# Servo_Cape.net
KiCad netlist of a schematic drawn in EAGLE
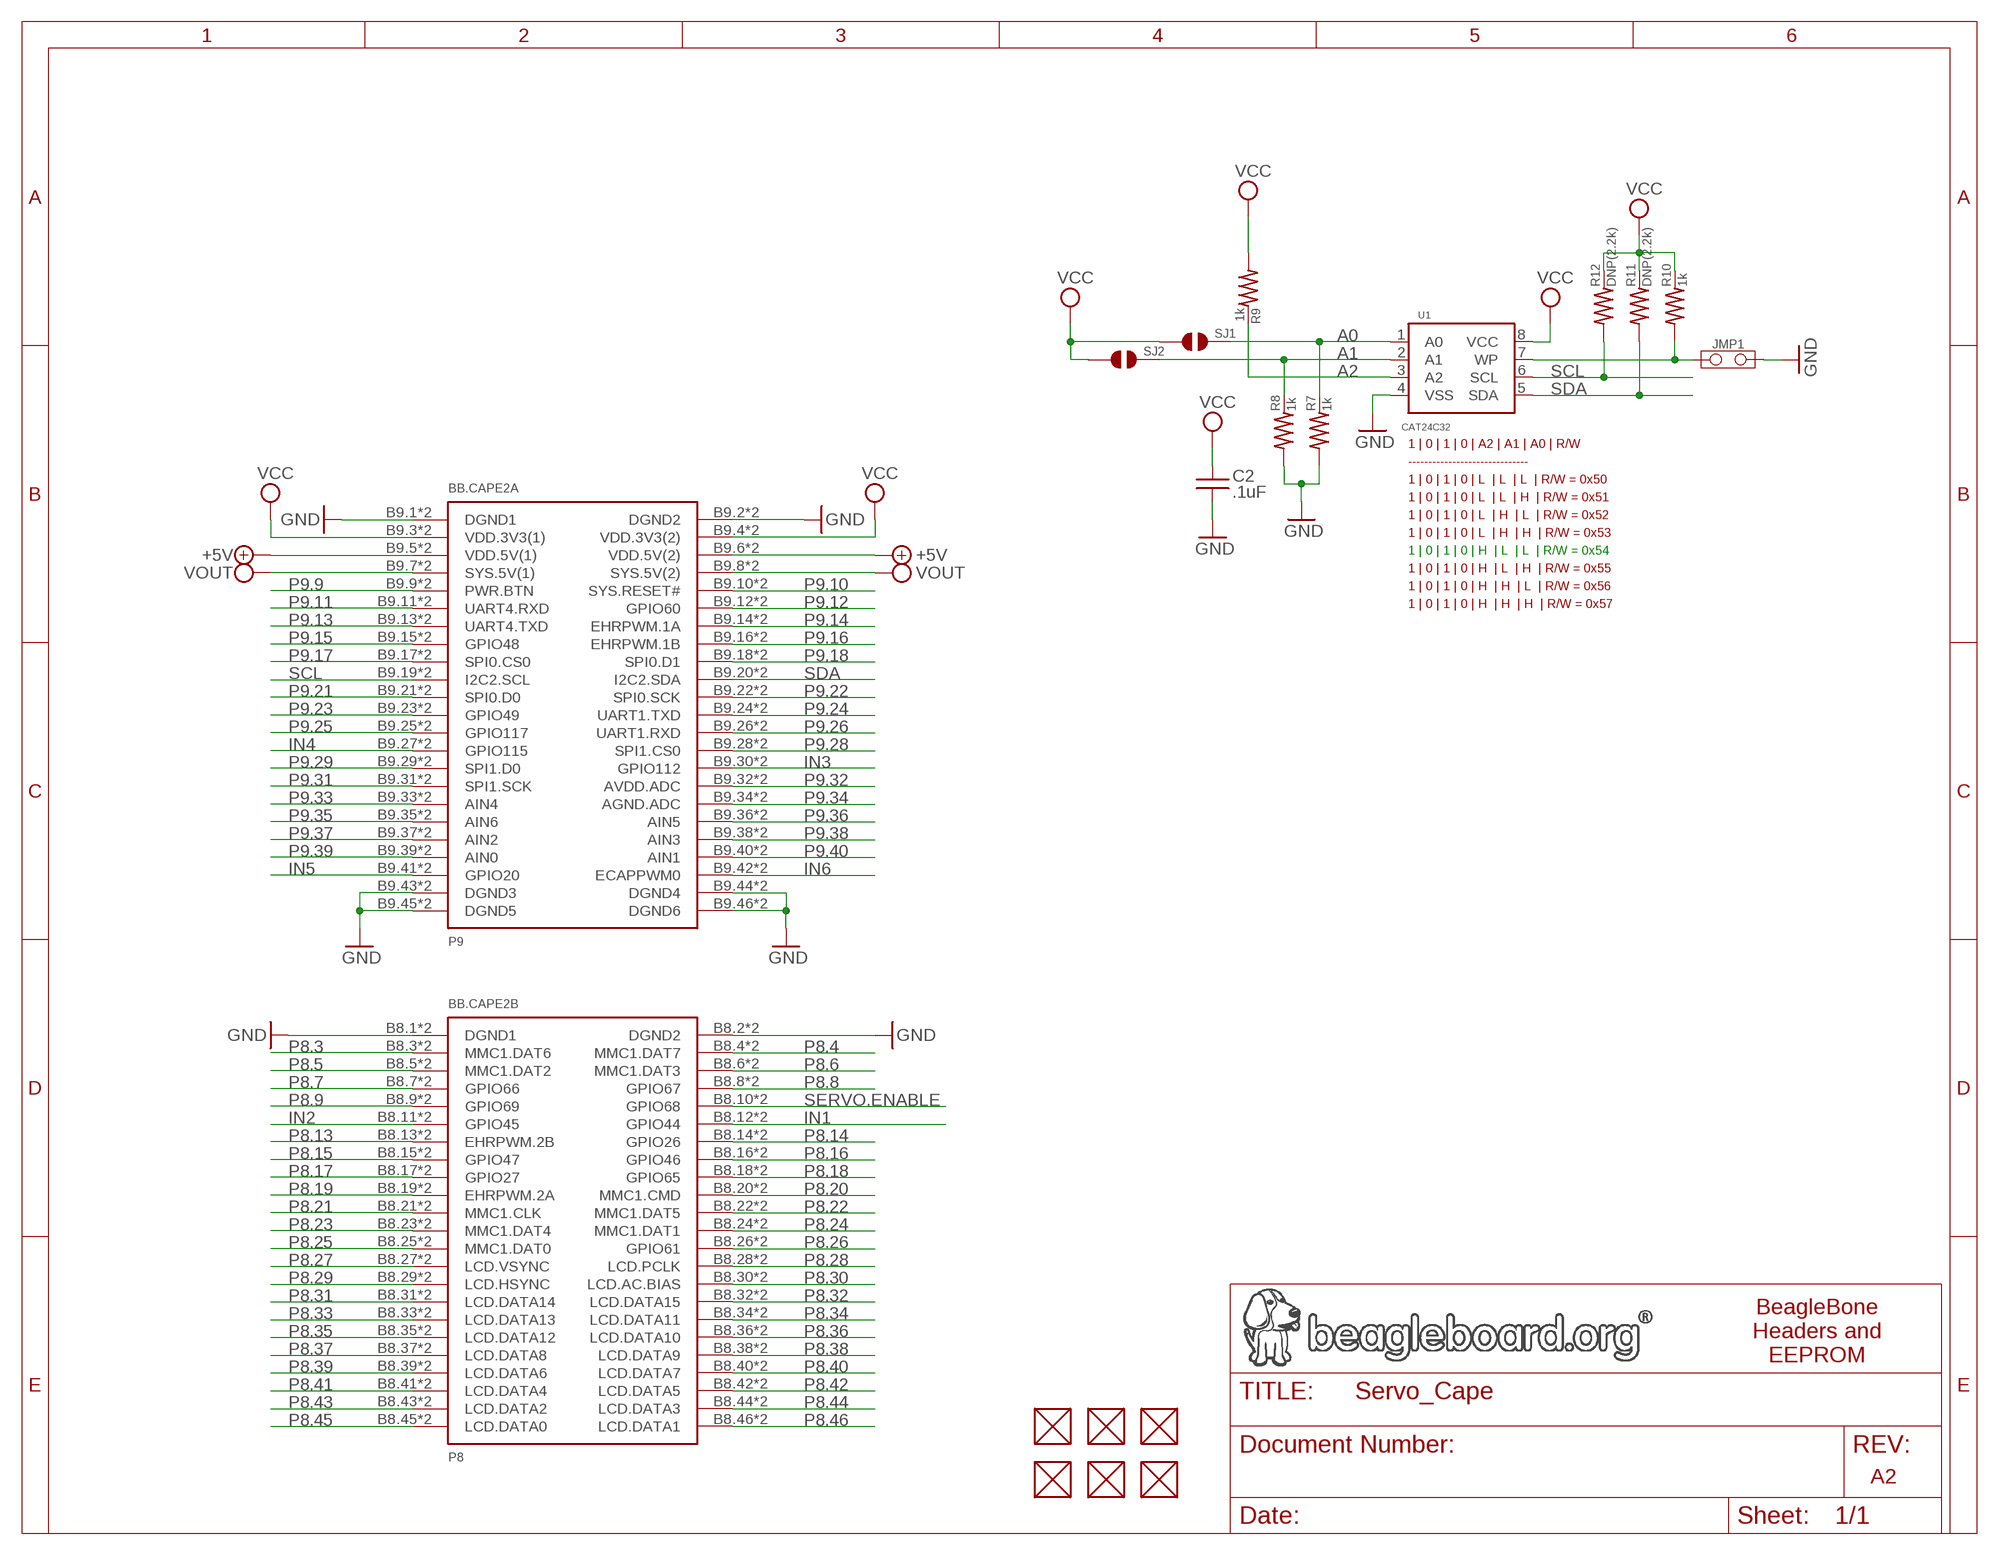
[diagram p0: schematic, sheet 1, part 1 of 2]
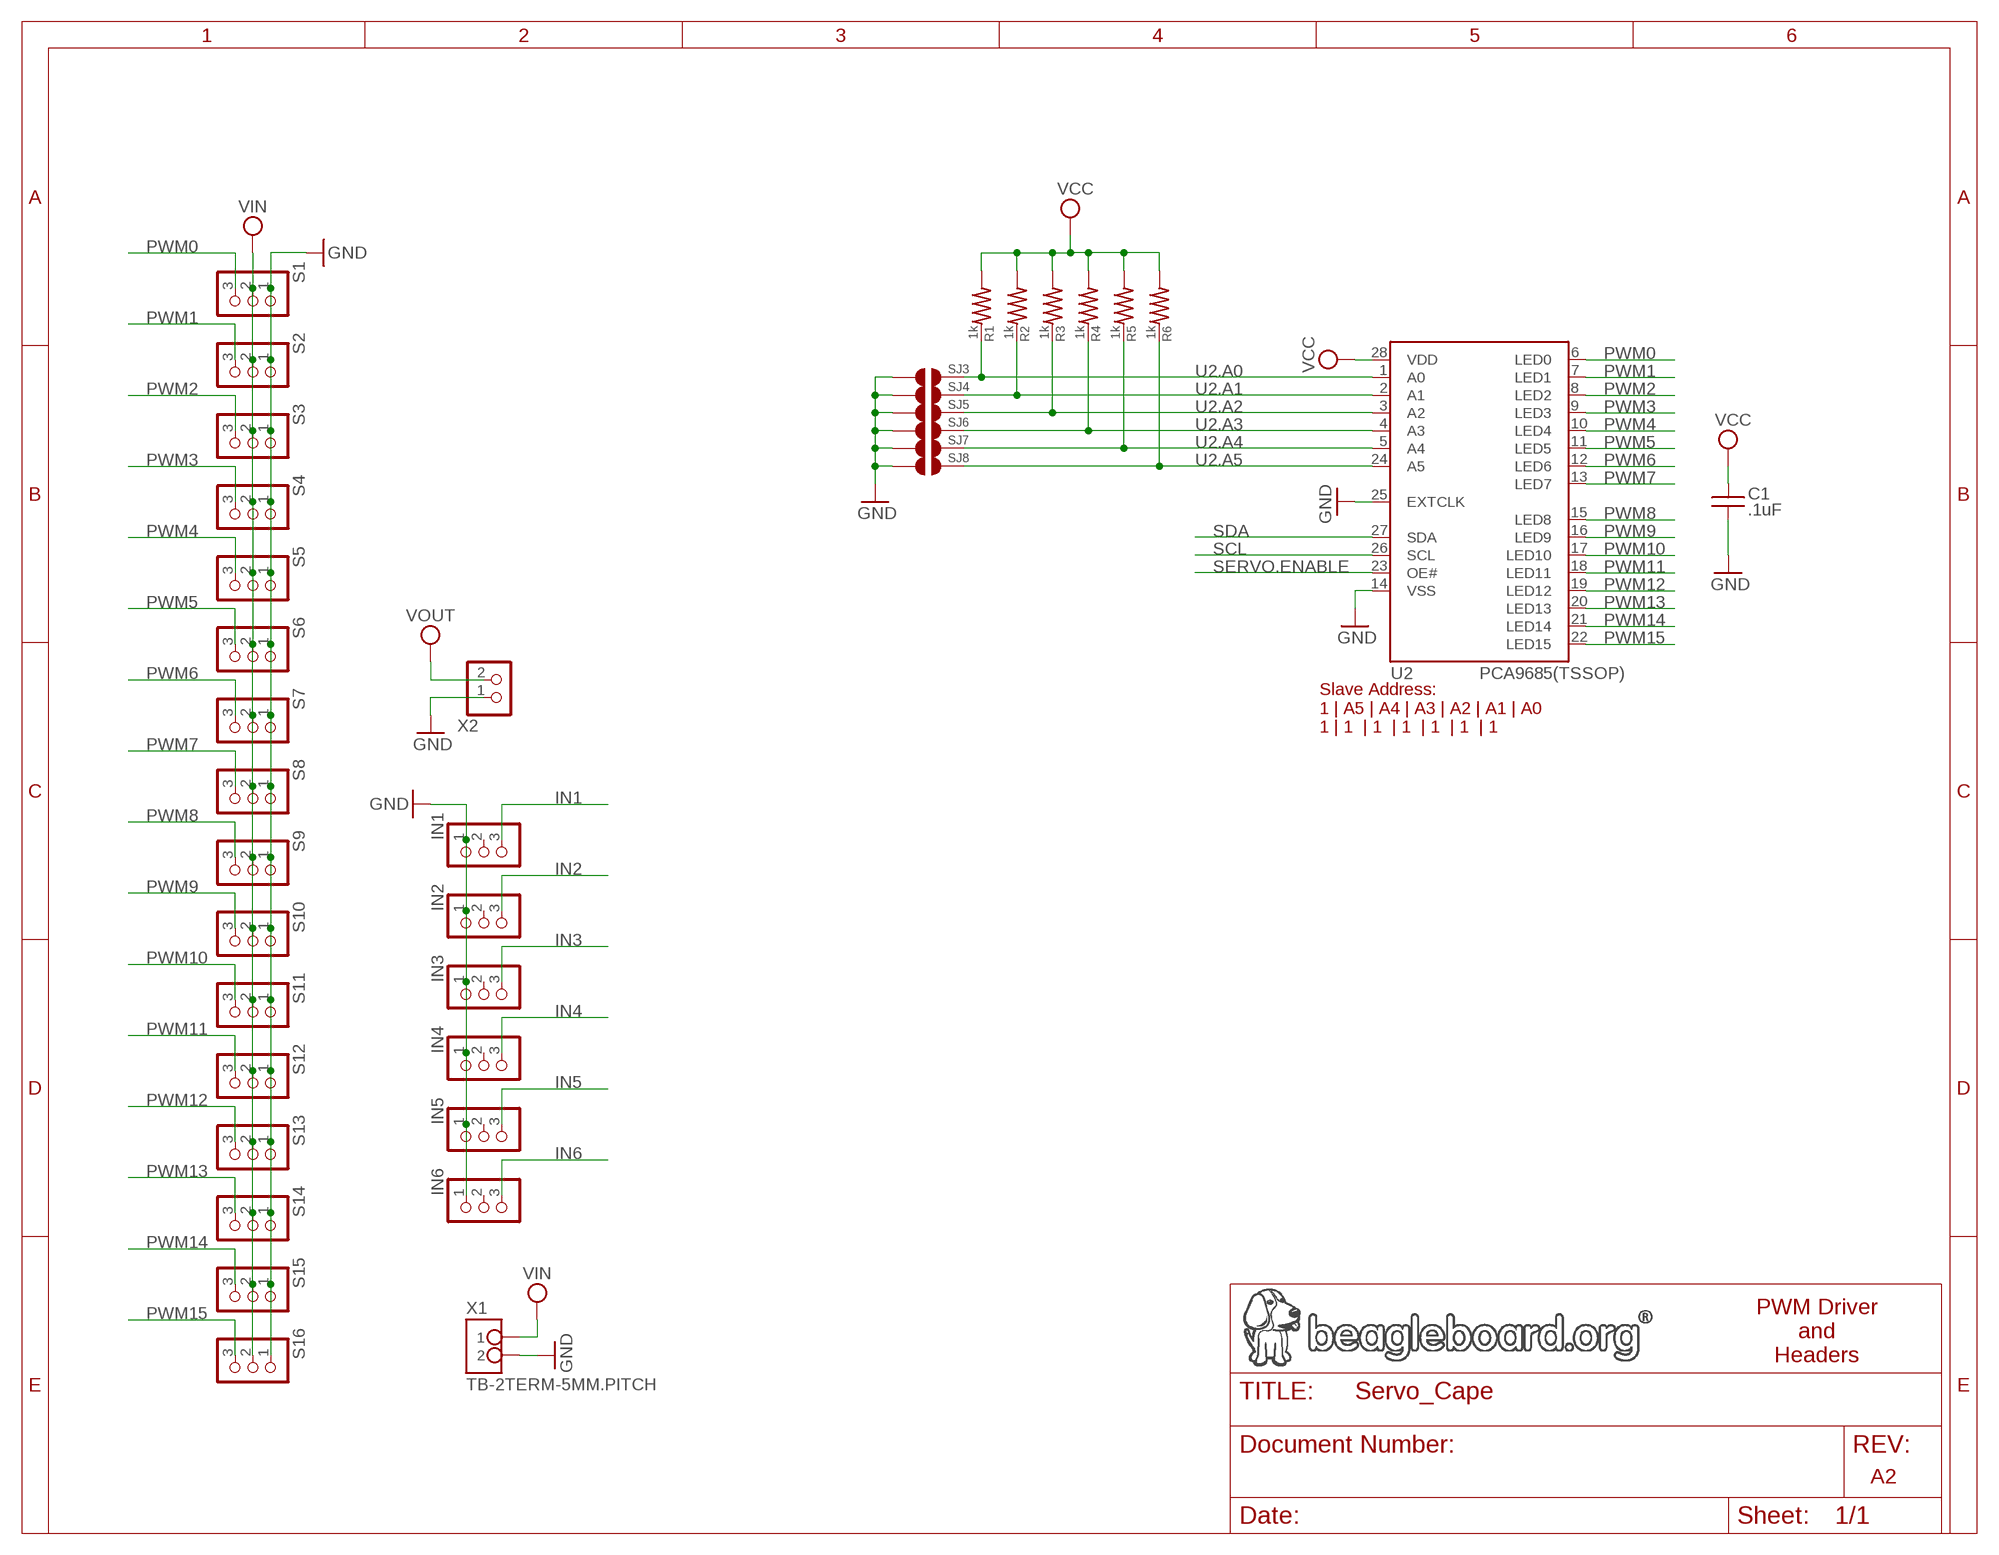
[diagram p1: schematic, sheet 1, part 2 of 2]

(export (version "E")
  (design (tool "Eeschema 10.0.6"))
  (components
    (comp (ref "BB.CAPE2")
      (value "BEAGLEBONE.CAPE.TOP/BOTTOM-PADS")
      (footprint "eagle-import:BEAGLEBONE.CAPE.TOP_BOTTOM-PADS")
      (libsource (lib "eagle-import") (part "BEAGLEBONE.CAPE.TOP/BOTTOM-PADS"))
    )
    (comp (ref "C1")
      (value ".1uF")
      (footprint "eagle-import:0402")
      (libsource (lib "eagle-import") (part "CAPACITOR-(INCH)-0402"))
    )
    (comp (ref "C2")
      (value ".1uF")
      (footprint "eagle-import:0402")
      (libsource (lib "eagle-import") (part "CAPACITOR-(INCH)-0402"))
    )
    (comp (ref "FUD1")
      (value "FIDUCIAL")
      (footprint "eagle-import:FIDUCIAL_40MIL")
      (libsource (lib "eagle-import") (part "FIDUCIAL"))
    )
    (comp (ref "FUD2")
      (value "FIDUCIAL")
      (footprint "eagle-import:FIDUCIAL_40MIL")
      (libsource (lib "eagle-import") (part "FIDUCIAL"))
    )
    (comp (ref "FUD3")
      (value "FIDUCIAL")
      (footprint "eagle-import:FIDUCIAL_40MIL")
      (libsource (lib "eagle-import") (part "FIDUCIAL"))
    )
    (comp (ref "FUD4")
      (value "FIDUCIAL")
      (footprint "eagle-import:FIDUCIAL_40MIL")
      (libsource (lib "eagle-import") (part "FIDUCIAL"))
    )
    (comp (ref "FUD5")
      (value "FIDUCIAL")
      (footprint "eagle-import:FIDUCIAL_40MIL")
      (libsource (lib "eagle-import") (part "FIDUCIAL"))
    )
    (comp (ref "FUD6")
      (value "FIDUCIAL")
      (footprint "eagle-import:FIDUCIAL_40MIL")
      (libsource (lib "eagle-import") (part "FIDUCIAL"))
    )
    (comp (ref "IN1")
      (value "1X3-(INCH)-0.1-TH-(35-MIL.DIA)")
      (footprint "eagle-import:TH-1X3-(35-MIL.DIA)")
      (libsource (lib "eagle-import") (part "1X3-(INCH)-0.1-TH-(35-MIL.DIA)"))
    )
    (comp (ref "IN2")
      (value "1X3-(INCH)-0.1-TH-(35-MIL.DIA)")
      (footprint "eagle-import:TH-1X3-(35-MIL.DIA)")
      (libsource (lib "eagle-import") (part "1X3-(INCH)-0.1-TH-(35-MIL.DIA)"))
    )
    (comp (ref "IN3")
      (value "1X3-(INCH)-0.1-TH-(35-MIL.DIA)")
      (footprint "eagle-import:TH-1X3-(35-MIL.DIA)")
      (libsource (lib "eagle-import") (part "1X3-(INCH)-0.1-TH-(35-MIL.DIA)"))
    )
    (comp (ref "IN4")
      (value "1X3-(INCH)-0.1-TH-(35-MIL.DIA)")
      (footprint "eagle-import:TH-1X3-(35-MIL.DIA)")
      (libsource (lib "eagle-import") (part "1X3-(INCH)-0.1-TH-(35-MIL.DIA)"))
    )
    (comp (ref "IN5")
      (value "1X3-(INCH)-0.1-TH-(35-MIL.DIA)")
      (footprint "eagle-import:TH-1X3-(35-MIL.DIA)")
      (libsource (lib "eagle-import") (part "1X3-(INCH)-0.1-TH-(35-MIL.DIA)"))
    )
    (comp (ref "IN6")
      (value "1X3-(INCH)-0.1-TH-(35-MIL.DIA)")
      (footprint "eagle-import:TH-1X3-(35-MIL.DIA)")
      (libsource (lib "eagle-import") (part "1X3-(INCH)-0.1-TH-(35-MIL.DIA)"))
    )
    (comp (ref "JMP1")
      (value "JUMPER-(X2)")
      (footprint "eagle-import:JUMPER-(X2)")
      (libsource (lib "eagle-import") (part "JUMPER-(X2)"))
    )
    (comp (ref "R1")
      (value "1k")
      (footprint "eagle-import:0402")
      (libsource (lib "eagle-import") (part "RESISTOR-(INCH)-0402"))
    )
    (comp (ref "R2")
      (value "1k")
      (footprint "eagle-import:0402")
      (libsource (lib "eagle-import") (part "RESISTOR-(INCH)-0402"))
    )
    (comp (ref "R3")
      (value "1k")
      (footprint "eagle-import:0402")
      (libsource (lib "eagle-import") (part "RESISTOR-(INCH)-0402"))
    )
    (comp (ref "R4")
      (value "1k")
      (footprint "eagle-import:0402")
      (libsource (lib "eagle-import") (part "RESISTOR-(INCH)-0402"))
    )
    (comp (ref "R5")
      (value "1k")
      (footprint "eagle-import:0402")
      (libsource (lib "eagle-import") (part "RESISTOR-(INCH)-0402"))
    )
    (comp (ref "R6")
      (value "1k")
      (footprint "eagle-import:0402")
      (libsource (lib "eagle-import") (part "RESISTOR-(INCH)-0402"))
    )
    (comp (ref "R7")
      (value "1k")
      (footprint "eagle-import:0402")
      (libsource (lib "eagle-import") (part "RESISTOR-(INCH)-0402"))
    )
    (comp (ref "R8")
      (value "1k")
      (footprint "eagle-import:0402")
      (libsource (lib "eagle-import") (part "RESISTOR-(INCH)-0402"))
    )
    (comp (ref "R9")
      (value "1k")
      (footprint "eagle-import:0402")
      (libsource (lib "eagle-import") (part "RESISTOR-(INCH)-0402"))
    )
    (comp (ref "R10")
      (value "1k")
      (footprint "eagle-import:0402")
      (libsource (lib "eagle-import") (part "RESISTOR-(INCH)-0402"))
    )
    (comp (ref "R11")
      (value "DNP(2.2k)")
      (footprint "eagle-import:0402")
      (libsource (lib "eagle-import") (part "RESISTOR-(INCH)-0402"))
    )
    (comp (ref "R12")
      (value "DNP(2.2k)")
      (footprint "eagle-import:0402")
      (libsource (lib "eagle-import") (part "RESISTOR-(INCH)-0402"))
    )
    (comp (ref "S1")
      (value "1X3-(INCH)-0.1-TH-(35-MIL.DIA)")
      (footprint "eagle-import:TH-1X3-(35-MIL.DIA)")
      (libsource (lib "eagle-import") (part "1X3-(INCH)-0.1-TH-(35-MIL.DIA)"))
    )
    (comp (ref "S2")
      (value "1X3-(INCH)-0.1-TH-(35-MIL.DIA)")
      (footprint "eagle-import:TH-1X3-(35-MIL.DIA)")
      (libsource (lib "eagle-import") (part "1X3-(INCH)-0.1-TH-(35-MIL.DIA)"))
    )
    (comp (ref "S3")
      (value "1X3-(INCH)-0.1-TH-(35-MIL.DIA)")
      (footprint "eagle-import:TH-1X3-(35-MIL.DIA)")
      (libsource (lib "eagle-import") (part "1X3-(INCH)-0.1-TH-(35-MIL.DIA)"))
    )
    (comp (ref "S4")
      (value "1X3-(INCH)-0.1-TH-(35-MIL.DIA)")
      (footprint "eagle-import:TH-1X3-(35-MIL.DIA)")
      (libsource (lib "eagle-import") (part "1X3-(INCH)-0.1-TH-(35-MIL.DIA)"))
    )
    (comp (ref "S5")
      (value "1X3-(INCH)-0.1-TH-(35-MIL.DIA)")
      (footprint "eagle-import:TH-1X3-(35-MIL.DIA)")
      (libsource (lib "eagle-import") (part "1X3-(INCH)-0.1-TH-(35-MIL.DIA)"))
    )
    (comp (ref "S6")
      (value "1X3-(INCH)-0.1-TH-(35-MIL.DIA)")
      (footprint "eagle-import:TH-1X3-(35-MIL.DIA)")
      (libsource (lib "eagle-import") (part "1X3-(INCH)-0.1-TH-(35-MIL.DIA)"))
    )
    (comp (ref "S7")
      (value "1X3-(INCH)-0.1-TH-(35-MIL.DIA)")
      (footprint "eagle-import:TH-1X3-(35-MIL.DIA)")
      (libsource (lib "eagle-import") (part "1X3-(INCH)-0.1-TH-(35-MIL.DIA)"))
    )
    (comp (ref "S8")
      (value "1X3-(INCH)-0.1-TH-(35-MIL.DIA)")
      (footprint "eagle-import:TH-1X3-(35-MIL.DIA)")
      (libsource (lib "eagle-import") (part "1X3-(INCH)-0.1-TH-(35-MIL.DIA)"))
    )
    (comp (ref "S9")
      (value "1X3-(INCH)-0.1-TH-(35-MIL.DIA)")
      (footprint "eagle-import:TH-1X3-(35-MIL.DIA)")
      (libsource (lib "eagle-import") (part "1X3-(INCH)-0.1-TH-(35-MIL.DIA)"))
    )
    (comp (ref "S10")
      (value "1X3-(INCH)-0.1-TH-(35-MIL.DIA)")
      (footprint "eagle-import:TH-1X3-(35-MIL.DIA)")
      (libsource (lib "eagle-import") (part "1X3-(INCH)-0.1-TH-(35-MIL.DIA)"))
    )
    (comp (ref "S11")
      (value "1X3-(INCH)-0.1-TH-(35-MIL.DIA)")
      (footprint "eagle-import:TH-1X3-(35-MIL.DIA)")
      (libsource (lib "eagle-import") (part "1X3-(INCH)-0.1-TH-(35-MIL.DIA)"))
    )
    (comp (ref "S12")
      (value "1X3-(INCH)-0.1-TH-(35-MIL.DIA)")
      (footprint "eagle-import:TH-1X3-(35-MIL.DIA)")
      (libsource (lib "eagle-import") (part "1X3-(INCH)-0.1-TH-(35-MIL.DIA)"))
    )
    (comp (ref "S13")
      (value "1X3-(INCH)-0.1-TH-(35-MIL.DIA)")
      (footprint "eagle-import:TH-1X3-(35-MIL.DIA)")
      (libsource (lib "eagle-import") (part "1X3-(INCH)-0.1-TH-(35-MIL.DIA)"))
    )
    (comp (ref "S14")
      (value "1X3-(INCH)-0.1-TH-(35-MIL.DIA)")
      (footprint "eagle-import:TH-1X3-(35-MIL.DIA)")
      (libsource (lib "eagle-import") (part "1X3-(INCH)-0.1-TH-(35-MIL.DIA)"))
    )
    (comp (ref "S15")
      (value "1X3-(INCH)-0.1-TH-(35-MIL.DIA)")
      (footprint "eagle-import:TH-1X3-(35-MIL.DIA)")
      (libsource (lib "eagle-import") (part "1X3-(INCH)-0.1-TH-(35-MIL.DIA)"))
    )
    (comp (ref "S16")
      (value "1X3-(INCH)-0.1-TH-(35-MIL.DIA)")
      (footprint "eagle-import:TH-1X3-(35-MIL.DIA)")
      (libsource (lib "eagle-import") (part "1X3-(INCH)-0.1-TH-(35-MIL.DIA)"))
    )
    (comp (ref "SJ1")
      (value "SOLDER.JOINT-(INCH)-0402")
      (footprint "eagle-import:SOLDER.JOINT(0402)")
      (libsource (lib "eagle-import") (part "SOLDER.JOINT-(INCH)-0402"))
    )
    (comp (ref "SJ2")
      (value "SOLDER.JOINT-(INCH)-0402")
      (footprint "eagle-import:SOLDER.JOINT(0402)")
      (libsource (lib "eagle-import") (part "SOLDER.JOINT-(INCH)-0402"))
    )
    (comp (ref "SJ3")
      (value "SOLDER.JOINT-(INCH)-0402")
      (footprint "eagle-import:SOLDER.JOINT(0402)")
      (libsource (lib "eagle-import") (part "SOLDER.JOINT-(INCH)-0402"))
    )
    (comp (ref "SJ4")
      (value "SOLDER.JOINT-(INCH)-0402")
      (footprint "eagle-import:SOLDER.JOINT(0402)")
      (libsource (lib "eagle-import") (part "SOLDER.JOINT-(INCH)-0402"))
    )
    (comp (ref "SJ5")
      (value "SOLDER.JOINT-(INCH)-0402")
      (footprint "eagle-import:SOLDER.JOINT(0402)")
      (libsource (lib "eagle-import") (part "SOLDER.JOINT-(INCH)-0402"))
    )
    (comp (ref "SJ6")
      (value "SOLDER.JOINT-(INCH)-0402")
      (footprint "eagle-import:SOLDER.JOINT(0402)")
      (libsource (lib "eagle-import") (part "SOLDER.JOINT-(INCH)-0402"))
    )
    (comp (ref "SJ7")
      (value "SOLDER.JOINT-(INCH)-0402")
      (footprint "eagle-import:SOLDER.JOINT(0402)")
      (libsource (lib "eagle-import") (part "SOLDER.JOINT-(INCH)-0402"))
    )
    (comp (ref "SJ8")
      (value "SOLDER.JOINT-(INCH)-0402")
      (footprint "eagle-import:SOLDER.JOINT(0402)")
      (libsource (lib "eagle-import") (part "SOLDER.JOINT-(INCH)-0402"))
    )
    (comp (ref "U1")
      (value "CAT24C32")
      (footprint "eagle-import:UDFN8,2X3(ON-SEMI)")
      (libsource (lib "eagle-import") (part "CAT24C32"))
    )
    (comp (ref "U2")
      (value "PCA9685(TSSOP)")
      (footprint "eagle-import:TSSOP28(NXP)")
      (libsource (lib "eagle-import") (part "PCA9685(TSSOP)"))
    )
    (comp (ref "X1")
      (value "TB-2TERM-5MM.PITCH")
      (footprint "eagle-import:TERMINAL.BLOCK-2TERM-5MM.PITCH")
      (libsource (lib "eagle-import") (part "TB-2TERM-5MM.PITCH"))
    )
    (comp (ref "X2")
      (value "1X2-(INCH)-0.1-TH-(35-MIL.DIA)")
      (footprint "eagle-import:TH-1X2-(35-MIL.DIA)")
      (libsource (lib "eagle-import") (part "1X2-(INCH)-0.1-TH-(35-MIL.DIA)"))
    )
  )
  (nets
    (net (code "1") (name "+5V") (class "Default")
      (node (ref "BB.CAPE2") (pin "B9.5") (pinfunction "VDD.5V(1)_B9.5") (pintype "bidirectional"))
      (node (ref "BB.CAPE2") (pin "B9.6") (pinfunction "VDD.5V(2)_B9.6") (pintype "bidirectional"))
      (node (ref "BB.CAPE2") (pin "T9.5") (pinfunction "VDD.5V(1)_T9.5") (pintype "bidirectional"))
      (node (ref "BB.CAPE2") (pin "T9.6") (pinfunction "VDD.5V(2)_T9.6") (pintype "bidirectional"))
    )
    (net (code "2") (name "/A0") (class "Default")
      (node (ref "R7") (pin "2") (pinfunction "2_2") (pintype "bidirectional"))
      (node (ref "SJ1") (pin "2") (pinfunction "2_2") (pintype "bidirectional"))
      (node (ref "U1") (pin "1") (pinfunction "A0_1") (pintype "bidirectional"))
    )
    (net (code "3") (name "/A1") (class "Default")
      (node (ref "R8") (pin "2") (pinfunction "2_2") (pintype "bidirectional"))
      (node (ref "SJ2") (pin "2") (pinfunction "2_2") (pintype "bidirectional"))
      (node (ref "U1") (pin "2") (pinfunction "A1_2") (pintype "bidirectional"))
    )
    (net (code "4") (name "/A2") (class "Default")
      (node (ref "R9") (pin "2") (pinfunction "2_2") (pintype "bidirectional"))
      (node (ref "U1") (pin "3") (pinfunction "A2_3") (pintype "bidirectional"))
    )
    (net (code "5") (name "/IN1") (class "Default")
      (node (ref "BB.CAPE2") (pin "B8.12") (pinfunction "GPIO44_B8.12") (pintype "bidirectional"))
      (node (ref "BB.CAPE2") (pin "T8.12") (pinfunction "GPIO44_T8.12") (pintype "bidirectional"))
      (node (ref "IN1") (pin "3") (pinfunction "3_3") (pintype "passive"))
    )
    (net (code "6") (name "/IN2") (class "Default")
      (node (ref "BB.CAPE2") (pin "B8.11") (pinfunction "GPIO45_B8.11") (pintype "bidirectional"))
      (node (ref "BB.CAPE2") (pin "T8.11") (pinfunction "GPIO45_T8.11") (pintype "bidirectional"))
      (node (ref "IN2") (pin "3") (pinfunction "3_3") (pintype "passive"))
    )
    (net (code "7") (name "/IN3") (class "Default")
      (node (ref "BB.CAPE2") (pin "B9.30") (pinfunction "GPIO112_B9.30") (pintype "bidirectional"))
      (node (ref "BB.CAPE2") (pin "T9.30") (pinfunction "GPIO112_T9.30") (pintype "bidirectional"))
      (node (ref "IN3") (pin "3") (pinfunction "3_3") (pintype "passive"))
    )
    (net (code "8") (name "/IN4") (class "Default")
      (node (ref "BB.CAPE2") (pin "B9.27") (pinfunction "GPIO115_B9.27") (pintype "bidirectional"))
      (node (ref "BB.CAPE2") (pin "T9.27") (pinfunction "GPIO115_T9.27") (pintype "bidirectional"))
      (node (ref "IN4") (pin "3") (pinfunction "3_3") (pintype "passive"))
    )
    (net (code "9") (name "/IN5") (class "Default")
      (node (ref "BB.CAPE2") (pin "B9.41") (pinfunction "GPIO20_B9.41") (pintype "bidirectional"))
      (node (ref "BB.CAPE2") (pin "T9.41") (pinfunction "GPIO20_T9.41") (pintype "bidirectional"))
      (node (ref "IN5") (pin "3") (pinfunction "3_3") (pintype "passive"))
    )
    (net (code "10") (name "/IN6") (class "Default")
      (node (ref "BB.CAPE2") (pin "B9.42") (pinfunction "ECAPPWM0_B9.42") (pintype "bidirectional"))
      (node (ref "BB.CAPE2") (pin "T9.42") (pinfunction "ECAPPWM0_T9.42") (pintype "bidirectional"))
      (node (ref "IN6") (pin "3") (pinfunction "3_3") (pintype "passive"))
    )
    (net (code "11") (name "/P8.3") (class "Default")
      (node (ref "BB.CAPE2") (pin "B8.3") (pinfunction "MMC1.DAT6_B8.3") (pintype "bidirectional"))
      (node (ref "BB.CAPE2") (pin "T8.3") (pinfunction "MMC1.DAT6_T8.3") (pintype "bidirectional"))
    )
    (net (code "12") (name "/P8.4") (class "Default")
      (node (ref "BB.CAPE2") (pin "B8.4") (pinfunction "MMC1.DAT7_B8.4") (pintype "bidirectional"))
      (node (ref "BB.CAPE2") (pin "T8.4") (pinfunction "MMC1.DAT7_T8.4") (pintype "bidirectional"))
    )
    (net (code "13") (name "/P8.5") (class "Default")
      (node (ref "BB.CAPE2") (pin "B8.5") (pinfunction "MMC1.DAT2_B8.5") (pintype "bidirectional"))
      (node (ref "BB.CAPE2") (pin "T8.5") (pinfunction "MMC1.DAT2_T8.5") (pintype "bidirectional"))
    )
    (net (code "14") (name "/P8.6") (class "Default")
      (node (ref "BB.CAPE2") (pin "B8.6") (pinfunction "MMC1.DAT3_B8.6") (pintype "bidirectional"))
      (node (ref "BB.CAPE2") (pin "T8.6") (pinfunction "MMC1.DAT3_T8.6") (pintype "bidirectional"))
    )
    (net (code "15") (name "/P8.7") (class "Default")
      (node (ref "BB.CAPE2") (pin "B8.7") (pinfunction "GPIO66_B8.7") (pintype "bidirectional"))
      (node (ref "BB.CAPE2") (pin "T8.7") (pinfunction "GPIO66_T8.7") (pintype "bidirectional"))
    )
    (net (code "16") (name "/P8.8") (class "Default")
      (node (ref "BB.CAPE2") (pin "B8.8") (pinfunction "GPIO67_B8.8") (pintype "bidirectional"))
      (node (ref "BB.CAPE2") (pin "T8.8") (pinfunction "GPIO67_T8.8") (pintype "bidirectional"))
    )
    (net (code "17") (name "/P8.9") (class "Default")
      (node (ref "BB.CAPE2") (pin "B8.9") (pinfunction "GPIO69_B8.9") (pintype "bidirectional"))
      (node (ref "BB.CAPE2") (pin "T8.9") (pinfunction "GPIO69_T8.9") (pintype "bidirectional"))
    )
    (net (code "18") (name "/P8.13") (class "Default")
      (node (ref "BB.CAPE2") (pin "B8.13") (pinfunction "EHRPWM.2B_B8.13") (pintype "bidirectional"))
      (node (ref "BB.CAPE2") (pin "T8.13") (pinfunction "EHRPWM.2B_T8.13") (pintype "bidirectional"))
    )
    (net (code "19") (name "/P8.14") (class "Default")
      (node (ref "BB.CAPE2") (pin "B8.14") (pinfunction "GPIO26_B8.14") (pintype "bidirectional"))
      (node (ref "BB.CAPE2") (pin "T8.14") (pinfunction "GPIO26_T8.14") (pintype "bidirectional"))
    )
    (net (code "20") (name "/P8.15") (class "Default")
      (node (ref "BB.CAPE2") (pin "B8.15") (pinfunction "GPIO47_B8.15") (pintype "bidirectional"))
      (node (ref "BB.CAPE2") (pin "T8.15") (pinfunction "GPIO47_T8.15") (pintype "bidirectional"))
    )
    (net (code "21") (name "/P8.16") (class "Default")
      (node (ref "BB.CAPE2") (pin "B8.16") (pinfunction "GPIO46_B8.16") (pintype "bidirectional"))
      (node (ref "BB.CAPE2") (pin "T8.16") (pinfunction "GPIO46_T8.16") (pintype "bidirectional"))
    )
    (net (code "22") (name "/P8.17") (class "Default")
      (node (ref "BB.CAPE2") (pin "B8.17") (pinfunction "GPIO27_B8.17") (pintype "bidirectional"))
      (node (ref "BB.CAPE2") (pin "T8.17") (pinfunction "GPIO27_T8.17") (pintype "bidirectional"))
    )
    (net (code "23") (name "/P8.18") (class "Default")
      (node (ref "BB.CAPE2") (pin "B8.18") (pinfunction "GPIO65_B8.18") (pintype "bidirectional"))
      (node (ref "BB.CAPE2") (pin "T8.18") (pinfunction "GPIO65_T8.18") (pintype "bidirectional"))
    )
    (net (code "24") (name "/P8.19") (class "Default")
      (node (ref "BB.CAPE2") (pin "B8.19") (pinfunction "EHRPWM.2A_B8.19") (pintype "bidirectional"))
      (node (ref "BB.CAPE2") (pin "T8.19") (pinfunction "EHRPWM.2A_T8.19") (pintype "bidirectional"))
    )
    (net (code "25") (name "/P8.20") (class "Default")
      (node (ref "BB.CAPE2") (pin "B8.20") (pinfunction "MMC1.CMD_B8.20") (pintype "bidirectional"))
      (node (ref "BB.CAPE2") (pin "T8.20") (pinfunction "MMC1.CMD_T8.20") (pintype "bidirectional"))
    )
    (net (code "26") (name "/P8.21") (class "Default")
      (node (ref "BB.CAPE2") (pin "B8.21") (pinfunction "MMC1.CLK_B8.21") (pintype "bidirectional"))
      (node (ref "BB.CAPE2") (pin "T8.21") (pinfunction "MMC1.CLK_T8.21") (pintype "bidirectional"))
    )
    (net (code "27") (name "/P8.22") (class "Default")
      (node (ref "BB.CAPE2") (pin "B8.22") (pinfunction "MMC1.DAT5_B8.22") (pintype "bidirectional"))
      (node (ref "BB.CAPE2") (pin "T8.22") (pinfunction "MMC1.DAT5_T8.22") (pintype "bidirectional"))
    )
    (net (code "28") (name "/P8.23") (class "Default")
      (node (ref "BB.CAPE2") (pin "B8.23") (pinfunction "MMC1.DAT4_B8.23") (pintype "bidirectional"))
      (node (ref "BB.CAPE2") (pin "T8.23") (pinfunction "MMC1.DAT4_T8.23") (pintype "bidirectional"))
    )
    (net (code "29") (name "/P8.24") (class "Default")
      (node (ref "BB.CAPE2") (pin "B8.24") (pinfunction "MMC1.DAT1_B8.24") (pintype "bidirectional"))
      (node (ref "BB.CAPE2") (pin "T8.24") (pinfunction "MMC1.DAT1_T8.24") (pintype "bidirectional"))
    )
    (net (code "30") (name "/P8.25") (class "Default")
      (node (ref "BB.CAPE2") (pin "B8.25") (pinfunction "MMC1.DAT0_B8.25") (pintype "bidirectional"))
      (node (ref "BB.CAPE2") (pin "T8.25") (pinfunction "MMC1.DAT0_T8.25") (pintype "bidirectional"))
    )
    (net (code "31") (name "/P8.26") (class "Default")
      (node (ref "BB.CAPE2") (pin "B8.26") (pinfunction "GPIO61_B8.26") (pintype "bidirectional"))
      (node (ref "BB.CAPE2") (pin "T8.26") (pinfunction "GPIO61_T8.26") (pintype "bidirectional"))
    )
    (net (code "32") (name "/P8.27") (class "Default")
      (node (ref "BB.CAPE2") (pin "B8.27") (pinfunction "LCD.VSYNC_B8.27") (pintype "bidirectional"))
      (node (ref "BB.CAPE2") (pin "T8.27") (pinfunction "LCD.VSYNC_T8.27") (pintype "bidirectional"))
    )
    (net (code "33") (name "/P8.28") (class "Default")
      (node (ref "BB.CAPE2") (pin "B8.28") (pinfunction "LCD.PCLK_B8.28") (pintype "bidirectional"))
      (node (ref "BB.CAPE2") (pin "T8.28") (pinfunction "LCD.PCLK_T8.28") (pintype "bidirectional"))
    )
    (net (code "34") (name "/P8.29") (class "Default")
      (node (ref "BB.CAPE2") (pin "B8.29") (pinfunction "LCD.HSYNC_B8.29") (pintype "bidirectional"))
      (node (ref "BB.CAPE2") (pin "T8.29") (pinfunction "LCD.HSYNC_T8.29") (pintype "bidirectional"))
    )
    (net (code "35") (name "/P8.30") (class "Default")
      (node (ref "BB.CAPE2") (pin "B8.30") (pinfunction "LCD.AC.BIAS_B8.30") (pintype "bidirectional"))
      (node (ref "BB.CAPE2") (pin "T8.30") (pinfunction "LCD.AC.BIAS_T8.30") (pintype "bidirectional"))
    )
    (net (code "36") (name "/P8.31") (class "Default")
      (node (ref "BB.CAPE2") (pin "B8.31") (pinfunction "LCD.DATA14_B8.31") (pintype "bidirectional"))
      (node (ref "BB.CAPE2") (pin "T8.31") (pinfunction "LCD.DATA14_T8.31") (pintype "bidirectional"))
    )
    (net (code "37") (name "/P8.32") (class "Default")
      (node (ref "BB.CAPE2") (pin "B8.32") (pinfunction "LCD.DATA15_B8.32") (pintype "bidirectional"))
      (node (ref "BB.CAPE2") (pin "T8.32") (pinfunction "LCD.DATA15_T8.32") (pintype "bidirectional"))
    )
    (net (code "38") (name "/P8.33") (class "Default")
      (node (ref "BB.CAPE2") (pin "B8.33") (pinfunction "LCD.DATA13_B8.33") (pintype "bidirectional"))
      (node (ref "BB.CAPE2") (pin "T8.33") (pinfunction "LCD.DATA13_T8.33") (pintype "bidirectional"))
    )
    (net (code "39") (name "/P8.34") (class "Default")
      (node (ref "BB.CAPE2") (pin "B8.34") (pinfunction "LCD.DATA11_B8.34") (pintype "bidirectional"))
      (node (ref "BB.CAPE2") (pin "T8.34") (pinfunction "LCD.DATA11_T8.34") (pintype "bidirectional"))
    )
    (net (code "40") (name "/P8.35") (class "Default")
      (node (ref "BB.CAPE2") (pin "B8.35") (pinfunction "LCD.DATA12_B8.35") (pintype "bidirectional"))
      (node (ref "BB.CAPE2") (pin "T8.35") (pinfunction "LCD.DATA12_T8.35") (pintype "bidirectional"))
    )
    (net (code "41") (name "/P8.36") (class "Default")
      (node (ref "BB.CAPE2") (pin "B8.36") (pinfunction "LCD.DATA10_B8.36") (pintype "bidirectional"))
      (node (ref "BB.CAPE2") (pin "T8.36") (pinfunction "LCD.DATA10_T8.36") (pintype "bidirectional"))
    )
    (net (code "42") (name "/P8.37") (class "Default")
      (node (ref "BB.CAPE2") (pin "B8.37") (pinfunction "LCD.DATA8_B8.37") (pintype "bidirectional"))
      (node (ref "BB.CAPE2") (pin "T8.37") (pinfunction "LCD.DATA8_T8.37") (pintype "bidirectional"))
    )
    (net (code "43") (name "/P8.38") (class "Default")
      (node (ref "BB.CAPE2") (pin "B8.38") (pinfunction "LCD.DATA9_B8.38") (pintype "bidirectional"))
      (node (ref "BB.CAPE2") (pin "T8.38") (pinfunction "LCD.DATA9_T8.38") (pintype "bidirectional"))
    )
    (net (code "44") (name "/P8.39") (class "Default")
      (node (ref "BB.CAPE2") (pin "B8.39") (pinfunction "LCD.DATA6_B8.39") (pintype "bidirectional"))
      (node (ref "BB.CAPE2") (pin "T8.39") (pinfunction "LCD.DATA6_T8.39") (pintype "bidirectional"))
    )
    (net (code "45") (name "/P8.40") (class "Default")
      (node (ref "BB.CAPE2") (pin "B8.40") (pinfunction "LCD.DATA7_B8.40") (pintype "bidirectional"))
      (node (ref "BB.CAPE2") (pin "T8.40") (pinfunction "LCD.DATA7_T8.40") (pintype "bidirectional"))
    )
    (net (code "46") (name "/P8.41") (class "Default")
      (node (ref "BB.CAPE2") (pin "B8.41") (pinfunction "LCD.DATA4_B8.41") (pintype "bidirectional"))
      (node (ref "BB.CAPE2") (pin "T8.41") (pinfunction "LCD.DATA4_T8.41") (pintype "bidirectional"))
    )
    (net (code "47") (name "/P8.42") (class "Default")
      (node (ref "BB.CAPE2") (pin "B8.42") (pinfunction "LCD.DATA5_B8.42") (pintype "bidirectional"))
      (node (ref "BB.CAPE2") (pin "T8.42") (pinfunction "LCD.DATA5_T8.42") (pintype "bidirectional"))
    )
    (net (code "48") (name "/P8.43") (class "Default")
      (node (ref "BB.CAPE2") (pin "B8.43") (pinfunction "LCD.DATA2_B8.43") (pintype "bidirectional"))
      (node (ref "BB.CAPE2") (pin "T8.43") (pinfunction "LCD.DATA2_T8.43") (pintype "bidirectional"))
    )
    (net (code "49") (name "/P8.44") (class "Default")
      (node (ref "BB.CAPE2") (pin "B8.44") (pinfunction "LCD.DATA3_B8.44") (pintype "bidirectional"))
      (node (ref "BB.CAPE2") (pin "T8.44") (pinfunction "LCD.DATA3_T8.44") (pintype "bidirectional"))
    )
    (net (code "50") (name "/P8.45") (class "Default")
      (node (ref "BB.CAPE2") (pin "B8.45") (pinfunction "LCD.DATA0_B8.45") (pintype "bidirectional"))
      (node (ref "BB.CAPE2") (pin "T8.45") (pinfunction "LCD.DATA0_T8.45") (pintype "bidirectional"))
    )
    (net (code "51") (name "/P8.46") (class "Default")
      (node (ref "BB.CAPE2") (pin "B8.46") (pinfunction "LCD.DATA1_B8.46") (pintype "bidirectional"))
      (node (ref "BB.CAPE2") (pin "T8.46") (pinfunction "LCD.DATA1_T8.46") (pintype "bidirectional"))
    )
    (net (code "52") (name "/P9.9") (class "Default")
      (node (ref "BB.CAPE2") (pin "B9.9") (pinfunction "PWR.BTN_B9.9") (pintype "bidirectional"))
      (node (ref "BB.CAPE2") (pin "T9.9") (pinfunction "PWR.BTN_T9.9") (pintype "bidirectional"))
    )
    (net (code "53") (name "/P9.10") (class "Default")
      (node (ref "BB.CAPE2") (pin "B9.10") (pinfunction "SYS.RESET#_B9.10") (pintype "bidirectional"))
      (node (ref "BB.CAPE2") (pin "T9.10") (pinfunction "SYS.RESET#_T9.10") (pintype "bidirectional"))
    )
    (net (code "54") (name "/P9.11") (class "Default")
      (node (ref "BB.CAPE2") (pin "B9.11") (pinfunction "UART4.RXD_B9.11") (pintype "bidirectional"))
      (node (ref "BB.CAPE2") (pin "T9.11") (pinfunction "UART4.RXD_T9.11") (pintype "bidirectional"))
    )
    (net (code "55") (name "/P9.12") (class "Default")
      (node (ref "BB.CAPE2") (pin "B9.12") (pinfunction "GPIO60_B9.12") (pintype "bidirectional"))
      (node (ref "BB.CAPE2") (pin "T9.12") (pinfunction "GPIO60_T9.12") (pintype "bidirectional"))
    )
    (net (code "56") (name "/P9.13") (class "Default")
      (node (ref "BB.CAPE2") (pin "B9.13") (pinfunction "UART4.TXD_B9.13") (pintype "bidirectional"))
      (node (ref "BB.CAPE2") (pin "T9.13") (pinfunction "UART4.TXD_T9.13") (pintype "bidirectional"))
    )
    (net (code "57") (name "/P9.14") (class "Default")
      (node (ref "BB.CAPE2") (pin "B9.14") (pinfunction "EHRPWM.1A_B9.14") (pintype "bidirectional"))
      (node (ref "BB.CAPE2") (pin "T9.14") (pinfunction "EHRPWM.1A_T9.14") (pintype "bidirectional"))
    )
    (net (code "58") (name "/P9.15") (class "Default")
      (node (ref "BB.CAPE2") (pin "B9.15") (pinfunction "GPIO48_B9.15") (pintype "bidirectional"))
      (node (ref "BB.CAPE2") (pin "T9.15") (pinfunction "GPIO48_T9.15") (pintype "bidirectional"))
    )
    (net (code "59") (name "/P9.16") (class "Default")
      (node (ref "BB.CAPE2") (pin "B9.16") (pinfunction "EHRPWM.1B_B9.16") (pintype "bidirectional"))
      (node (ref "BB.CAPE2") (pin "T9.16") (pinfunction "EHRPWM.1B_T9.16") (pintype "bidirectional"))
    )
    (net (code "60") (name "/P9.17") (class "Default")
      (node (ref "BB.CAPE2") (pin "B9.17") (pinfunction "SPI0.CS0_B9.17") (pintype "bidirectional"))
      (node (ref "BB.CAPE2") (pin "T9.17") (pinfunction "SPI0.CS0_T9.17") (pintype "bidirectional"))
    )
    (net (code "61") (name "/P9.18") (class "Default")
      (node (ref "BB.CAPE2") (pin "B9.18") (pinfunction "SPI0.D1_B9.18") (pintype "bidirectional"))
      (node (ref "BB.CAPE2") (pin "T9.18") (pinfunction "SPI0.D1_T9.18") (pintype "bidirectional"))
    )
    (net (code "62") (name "/P9.21") (class "Default")
      (node (ref "BB.CAPE2") (pin "B9.21") (pinfunction "SPI0.D0_B9.21") (pintype "bidirectional"))
      (node (ref "BB.CAPE2") (pin "T9.21") (pinfunction "SPI0.D0_T9.21") (pintype "bidirectional"))
    )
    (net (code "63") (name "/P9.22") (class "Default")
      (node (ref "BB.CAPE2") (pin "B9.22") (pinfunction "SPI0.SCK_B9.22") (pintype "bidirectional"))
      (node (ref "BB.CAPE2") (pin "T9.22") (pinfunction "SPI0.SCK_T9.22") (pintype "bidirectional"))
    )
    (net (code "64") (name "/P9.23") (class "Default")
      (node (ref "BB.CAPE2") (pin "B9.23") (pinfunction "GPIO49_B9.23") (pintype "bidirectional"))
      (node (ref "BB.CAPE2") (pin "T9.23") (pinfunction "GPIO49_T9.23") (pintype "bidirectional"))
    )
    (net (code "65") (name "/P9.24") (class "Default")
      (node (ref "BB.CAPE2") (pin "B9.24") (pinfunction "UART1.TXD_B9.24") (pintype "bidirectional"))
      (node (ref "BB.CAPE2") (pin "T9.24") (pinfunction "UART1.TXD_T9.24") (pintype "bidirectional"))
    )
    (net (code "66") (name "/P9.25") (class "Default")
      (node (ref "BB.CAPE2") (pin "B9.25") (pinfunction "GPIO117_B9.25") (pintype "bidirectional"))
      (node (ref "BB.CAPE2") (pin "T9.25") (pinfunction "GPIO117_T9.25") (pintype "bidirectional"))
    )
    (net (code "67") (name "/P9.26") (class "Default")
      (node (ref "BB.CAPE2") (pin "B9.26") (pinfunction "UART1.RXD_B9.26") (pintype "bidirectional"))
      (node (ref "BB.CAPE2") (pin "T9.26") (pinfunction "UART1.RXD_T9.26") (pintype "bidirectional"))
    )
    (net (code "68") (name "/P9.28") (class "Default")
      (node (ref "BB.CAPE2") (pin "B9.28") (pinfunction "SPI1.CS0_B9.28") (pintype "bidirectional"))
      (node (ref "BB.CAPE2") (pin "T9.28") (pinfunction "SPI1.CS0_T9.28") (pintype "bidirectional"))
    )
    (net (code "69") (name "/P9.29") (class "Default")
      (node (ref "BB.CAPE2") (pin "B9.29") (pinfunction "SPI1.D0_B9.29") (pintype "bidirectional"))
      (node (ref "BB.CAPE2") (pin "T9.29") (pinfunction "SPI1.D0_T9.29") (pintype "bidirectional"))
    )
    (net (code "70") (name "/P9.31") (class "Default")
      (node (ref "BB.CAPE2") (pin "B9.31") (pinfunction "SPI1.SCK_B9.31") (pintype "bidirectional"))
      (node (ref "BB.CAPE2") (pin "T9.31") (pinfunction "SPI1.SCK_T9.31") (pintype "bidirectional"))
    )
    (net (code "71") (name "/P9.32") (class "Default")
      (node (ref "BB.CAPE2") (pin "B9.32") (pinfunction "AVDD.ADC_B9.32") (pintype "bidirectional"))
      (node (ref "BB.CAPE2") (pin "T9.32") (pinfunction "AVDD.ADC_T9.32") (pintype "bidirectional"))
    )
    (net (code "72") (name "/P9.33") (class "Default")
      (node (ref "BB.CAPE2") (pin "B9.33") (pinfunction "AIN4_B9.33") (pintype "bidirectional"))
      (node (ref "BB.CAPE2") (pin "T9.33") (pinfunction "AIN4_T9.33") (pintype "bidirectional"))
    )
    (net (code "73") (name "/P9.34") (class "Default")
      (node (ref "BB.CAPE2") (pin "B9.34") (pinfunction "AGND.ADC_B9.34") (pintype "bidirectional"))
      (node (ref "BB.CAPE2") (pin "T9.34") (pinfunction "AGND.ADC_T9.34") (pintype "bidirectional"))
    )
    (net (code "74") (name "/P9.35") (class "Default")
      (node (ref "BB.CAPE2") (pin "B9.35") (pinfunction "AIN6_B9.35") (pintype "bidirectional"))
      (node (ref "BB.CAPE2") (pin "T9.35") (pinfunction "AIN6_T9.35") (pintype "bidirectional"))
    )
    (net (code "75") (name "/P9.36") (class "Default")
      (node (ref "BB.CAPE2") (pin "B9.36") (pinfunction "AIN5_B9.36") (pintype "bidirectional"))
      (node (ref "BB.CAPE2") (pin "T9.36") (pinfunction "AIN5_T9.36") (pintype "bidirectional"))
    )
    (net (code "76") (name "/P9.37") (class "Default")
      (node (ref "BB.CAPE2") (pin "B9.37") (pinfunction "AIN2_B9.37") (pintype "bidirectional"))
      (node (ref "BB.CAPE2") (pin "T9.37") (pinfunction "AIN2_T9.37") (pintype "bidirectional"))
    )
    (net (code "77") (name "/P9.38") (class "Default")
      (node (ref "BB.CAPE2") (pin "B9.38") (pinfunction "AIN3_B9.38") (pintype "bidirectional"))
      (node (ref "BB.CAPE2") (pin "T9.38") (pinfunction "AIN3_T9.38") (pintype "bidirectional"))
    )
    (net (code "78") (name "/P9.39") (class "Default")
      (node (ref "BB.CAPE2") (pin "B9.39") (pinfunction "AIN0_B9.39") (pintype "bidirectional"))
      (node (ref "BB.CAPE2") (pin "T9.39") (pinfunction "AIN0_T9.39") (pintype "bidirectional"))
    )
    (net (code "79") (name "/P9.40") (class "Default")
      (node (ref "BB.CAPE2") (pin "B9.40") (pinfunction "AIN1_B9.40") (pintype "bidirectional"))
      (node (ref "BB.CAPE2") (pin "T9.40") (pinfunction "AIN1_T9.40") (pintype "bidirectional"))
    )
    (net (code "80") (name "/PWM0") (class "Default")
      (node (ref "S1") (pin "3") (pinfunction "3_3") (pintype "passive"))
      (node (ref "U2") (pin "6") (pinfunction "LED0_6") (pintype "bidirectional"))
    )
    (net (code "81") (name "/PWM1") (class "Default")
      (node (ref "S2") (pin "3") (pinfunction "3_3") (pintype "passive"))
      (node (ref "U2") (pin "7") (pinfunction "LED1_7") (pintype "bidirectional"))
    )
    (net (code "82") (name "/PWM2") (class "Default")
      (node (ref "S3") (pin "3") (pinfunction "3_3") (pintype "passive"))
      (node (ref "U2") (pin "8") (pinfunction "LED2_8") (pintype "bidirectional"))
    )
    (net (code "83") (name "/PWM3") (class "Default")
      (node (ref "S4") (pin "3") (pinfunction "3_3") (pintype "passive"))
      (node (ref "U2") (pin "9") (pinfunction "LED3_9") (pintype "bidirectional"))
    )
    (net (code "84") (name "/PWM4") (class "Default")
      (node (ref "S5") (pin "3") (pinfunction "3_3") (pintype "passive"))
      (node (ref "U2") (pin "10") (pinfunction "LED4_10") (pintype "bidirectional"))
    )
    (net (code "85") (name "/PWM5") (class "Default")
      (node (ref "S6") (pin "3") (pinfunction "3_3") (pintype "passive"))
      (node (ref "U2") (pin "11") (pinfunction "LED5_11") (pintype "bidirectional"))
    )
    (net (code "86") (name "/PWM6") (class "Default")
      (node (ref "S7") (pin "3") (pinfunction "3_3") (pintype "passive"))
      (node (ref "U2") (pin "12") (pinfunction "LED6_12") (pintype "bidirectional"))
    )
    (net (code "87") (name "/PWM7") (class "Default")
      (node (ref "S8") (pin "3") (pinfunction "3_3") (pintype "passive"))
      (node (ref "U2") (pin "13") (pinfunction "LED7_13") (pintype "bidirectional"))
    )
    (net (code "88") (name "/PWM8") (class "Default")
      (node (ref "S9") (pin "3") (pinfunction "3_3") (pintype "passive"))
      (node (ref "U2") (pin "15") (pinfunction "LED8_15") (pintype "bidirectional"))
    )
    (net (code "89") (name "/PWM9") (class "Default")
      (node (ref "S10") (pin "3") (pinfunction "3_3") (pintype "passive"))
      (node (ref "U2") (pin "16") (pinfunction "LED9_16") (pintype "bidirectional"))
    )
    (net (code "90") (name "/PWM10") (class "Default")
      (node (ref "S11") (pin "3") (pinfunction "3_3") (pintype "passive"))
      (node (ref "U2") (pin "17") (pinfunction "LED10_17") (pintype "bidirectional"))
    )
    (net (code "91") (name "/PWM11") (class "Default")
      (node (ref "S12") (pin "3") (pinfunction "3_3") (pintype "passive"))
      (node (ref "U2") (pin "18") (pinfunction "LED11_18") (pintype "bidirectional"))
    )
    (net (code "92") (name "/PWM12") (class "Default")
      (node (ref "S13") (pin "3") (pinfunction "3_3") (pintype "passive"))
      (node (ref "U2") (pin "19") (pinfunction "LED12_19") (pintype "bidirectional"))
    )
    (net (code "93") (name "/PWM13") (class "Default")
      (node (ref "S14") (pin "3") (pinfunction "3_3") (pintype "passive"))
      (node (ref "U2") (pin "20") (pinfunction "LED13_20") (pintype "bidirectional"))
    )
    (net (code "94") (name "/PWM14") (class "Default")
      (node (ref "S15") (pin "3") (pinfunction "3_3") (pintype "passive"))
      (node (ref "U2") (pin "21") (pinfunction "LED14_21") (pintype "bidirectional"))
    )
    (net (code "95") (name "/PWM15") (class "Default")
      (node (ref "S16") (pin "3") (pinfunction "3_3") (pintype "passive"))
      (node (ref "U2") (pin "22") (pinfunction "LED15_22") (pintype "bidirectional"))
    )
    (net (code "96") (name "/SCL") (class "Default")
      (node (ref "BB.CAPE2") (pin "B9.19") (pinfunction "I2C2.SCL_B9.19") (pintype "bidirectional"))
      (node (ref "BB.CAPE2") (pin "T9.19") (pinfunction "I2C2.SCL_T9.19") (pintype "bidirectional"))
      (node (ref "R12") (pin "1") (pinfunction "1_1") (pintype "bidirectional"))
      (node (ref "U1") (pin "6") (pinfunction "SCL_6") (pintype "bidirectional"))
      (node (ref "U2") (pin "26") (pinfunction "SCL_26") (pintype "bidirectional"))
    )
    (net (code "97") (name "/SDA") (class "Default")
      (node (ref "BB.CAPE2") (pin "B9.20") (pinfunction "I2C2.SDA_B9.20") (pintype "bidirectional"))
      (node (ref "BB.CAPE2") (pin "T9.20") (pinfunction "I2C2.SDA_T9.20") (pintype "bidirectional"))
      (node (ref "R11") (pin "1") (pinfunction "1_1") (pintype "bidirectional"))
      (node (ref "U1") (pin "5") (pinfunction "SDA_5") (pintype "bidirectional"))
      (node (ref "U2") (pin "27") (pinfunction "SDA_27") (pintype "bidirectional"))
    )
    (net (code "98") (name "/SERVO.ENABLE") (class "Default")
      (node (ref "BB.CAPE2") (pin "B8.10") (pinfunction "GPIO68_B8.10") (pintype "bidirectional"))
      (node (ref "BB.CAPE2") (pin "T8.10") (pinfunction "GPIO68_T8.10") (pintype "bidirectional"))
      (node (ref "U2") (pin "23") (pinfunction "OE#_23") (pintype "bidirectional"))
    )
    (net (code "99") (name "/U2.A0") (class "Default")
      (node (ref "R1") (pin "2") (pinfunction "2_2") (pintype "bidirectional"))
      (node (ref "SJ3") (pin "2") (pinfunction "2_2") (pintype "bidirectional"))
      (node (ref "U2") (pin "1") (pinfunction "A0_1") (pintype "bidirectional"))
    )
    (net (code "100") (name "/U2.A1") (class "Default")
      (node (ref "R2") (pin "2") (pinfunction "2_2") (pintype "bidirectional"))
      (node (ref "SJ4") (pin "2") (pinfunction "2_2") (pintype "bidirectional"))
      (node (ref "U2") (pin "2") (pinfunction "A1_2") (pintype "bidirectional"))
    )
    (net (code "101") (name "/U2.A2") (class "Default")
      (node (ref "R3") (pin "2") (pinfunction "2_2") (pintype "bidirectional"))
      (node (ref "SJ5") (pin "2") (pinfunction "2_2") (pintype "bidirectional"))
      (node (ref "U2") (pin "3") (pinfunction "A2_3") (pintype "bidirectional"))
    )
    (net (code "102") (name "/U2.A3") (class "Default")
      (node (ref "R4") (pin "2") (pinfunction "2_2") (pintype "bidirectional"))
      (node (ref "SJ6") (pin "2") (pinfunction "2_2") (pintype "bidirectional"))
      (node (ref "U2") (pin "4") (pinfunction "A3_4") (pintype "bidirectional"))
    )
    (net (code "103") (name "/U2.A4") (class "Default")
      (node (ref "R5") (pin "2") (pinfunction "2_2") (pintype "bidirectional"))
      (node (ref "SJ7") (pin "2") (pinfunction "2_2") (pintype "bidirectional"))
      (node (ref "U2") (pin "5") (pinfunction "A4_5") (pintype "bidirectional"))
    )
    (net (code "104") (name "/U2.A5") (class "Default")
      (node (ref "R6") (pin "2") (pinfunction "2_2") (pintype "bidirectional"))
      (node (ref "SJ8") (pin "2") (pinfunction "2_2") (pintype "bidirectional"))
      (node (ref "U2") (pin "24") (pinfunction "A5_24") (pintype "bidirectional"))
    )
    (net (code "105") (name "GND") (class "Default")
      (node (ref "BB.CAPE2") (pin "B8.1") (pinfunction "DGND1_B8.1") (pintype "bidirectional"))
      (node (ref "BB.CAPE2") (pin "B8.2") (pinfunction "DGND2_B8.2") (pintype "bidirectional"))
      (node (ref "BB.CAPE2") (pin "B9.1") (pinfunction "DGND1_B9.1") (pintype "bidirectional"))
      (node (ref "BB.CAPE2") (pin "B9.2") (pinfunction "DGND2_B9.2") (pintype "bidirectional"))
      (node (ref "BB.CAPE2") (pin "B9.43") (pinfunction "DGND3_B9.43") (pintype "bidirectional"))
      (node (ref "BB.CAPE2") (pin "B9.44") (pinfunction "DGND4_B9.44") (pintype "bidirectional"))
      (node (ref "BB.CAPE2") (pin "B9.45") (pinfunction "DGND5_B9.45") (pintype "bidirectional"))
      (node (ref "BB.CAPE2") (pin "B9.46") (pinfunction "DGND6_B9.46") (pintype "bidirectional"))
      (node (ref "BB.CAPE2") (pin "T8.1") (pinfunction "DGND1_T8.1") (pintype "bidirectional"))
      (node (ref "BB.CAPE2") (pin "T8.2") (pinfunction "DGND2_T8.2") (pintype "bidirectional"))
      (node (ref "BB.CAPE2") (pin "T9.1") (pinfunction "DGND1_T9.1") (pintype "bidirectional"))
      (node (ref "BB.CAPE2") (pin "T9.2") (pinfunction "DGND2_T9.2") (pintype "bidirectional"))
      (node (ref "BB.CAPE2") (pin "T9.43") (pinfunction "DGND3_T9.43") (pintype "bidirectional"))
      (node (ref "BB.CAPE2") (pin "T9.44") (pinfunction "DGND4_T9.44") (pintype "bidirectional"))
      (node (ref "BB.CAPE2") (pin "T9.45") (pinfunction "DGND5_T9.45") (pintype "bidirectional"))
      (node (ref "BB.CAPE2") (pin "T9.46") (pinfunction "DGND6_T9.46") (pintype "bidirectional"))
      (node (ref "C1") (pin "2") (pinfunction "2_2") (pintype "bidirectional"))
      (node (ref "C2") (pin "2") (pinfunction "2_2") (pintype "bidirectional"))
      (node (ref "IN1") (pin "1") (pinfunction "1_1") (pintype "passive"))
      (node (ref "IN2") (pin "1") (pinfunction "1_1") (pintype "passive"))
      (node (ref "IN3") (pin "1") (pinfunction "1_1") (pintype "passive"))
      (node (ref "IN4") (pin "1") (pinfunction "1_1") (pintype "passive"))
      (node (ref "IN5") (pin "1") (pinfunction "1_1") (pintype "passive"))
      (node (ref "IN6") (pin "1") (pinfunction "1_1") (pintype "passive"))
      (node (ref "JMP1") (pin "2") (pinfunction "2_2") (pintype "bidirectional"))
      (node (ref "R7") (pin "1") (pinfunction "1_1") (pintype "bidirectional"))
      (node (ref "R8") (pin "1") (pinfunction "1_1") (pintype "bidirectional"))
      (node (ref "S1") (pin "1") (pinfunction "1_1") (pintype "passive"))
      (node (ref "S10") (pin "1") (pinfunction "1_1") (pintype "passive"))
      (node (ref "S11") (pin "1") (pinfunction "1_1") (pintype "passive"))
      (node (ref "S12") (pin "1") (pinfunction "1_1") (pintype "passive"))
      (node (ref "S13") (pin "1") (pinfunction "1_1") (pintype "passive"))
      (node (ref "S14") (pin "1") (pinfunction "1_1") (pintype "passive"))
      (node (ref "S15") (pin "1") (pinfunction "1_1") (pintype "passive"))
      (node (ref "S16") (pin "1") (pinfunction "1_1") (pintype "passive"))
      (node (ref "S2") (pin "1") (pinfunction "1_1") (pintype "passive"))
      (node (ref "S3") (pin "1") (pinfunction "1_1") (pintype "passive"))
      (node (ref "S4") (pin "1") (pinfunction "1_1") (pintype "passive"))
      (node (ref "S5") (pin "1") (pinfunction "1_1") (pintype "passive"))
      (node (ref "S6") (pin "1") (pinfunction "1_1") (pintype "passive"))
      (node (ref "S7") (pin "1") (pinfunction "1_1") (pintype "passive"))
      (node (ref "S8") (pin "1") (pinfunction "1_1") (pintype "passive"))
      (node (ref "S9") (pin "1") (pinfunction "1_1") (pintype "passive"))
      (node (ref "SJ3") (pin "1") (pinfunction "1_1") (pintype "bidirectional"))
      (node (ref "SJ4") (pin "1") (pinfunction "1_1") (pintype "bidirectional"))
      (node (ref "SJ5") (pin "1") (pinfunction "1_1") (pintype "bidirectional"))
      (node (ref "SJ6") (pin "1") (pinfunction "1_1") (pintype "bidirectional"))
      (node (ref "SJ7") (pin "1") (pinfunction "1_1") (pintype "bidirectional"))
      (node (ref "SJ8") (pin "1") (pinfunction "1_1") (pintype "bidirectional"))
      (node (ref "U1") (pin "4") (pinfunction "VSS_4") (pintype "bidirectional"))
      (node (ref "U2") (pin "14") (pinfunction "VSS_14") (pintype "bidirectional"))
      (node (ref "U2") (pin "25") (pinfunction "EXTCLK_25") (pintype "bidirectional"))
      (node (ref "X1") (pin "2") (pinfunction "2_2") (pintype "bidirectional"))
      (node (ref "X2") (pin "1") (pinfunction "1_1") (pintype "passive"))
    )
    (net (code "106") (name "Net-(U1-WP)") (class "Default")
      (node (ref "JMP1") (pin "1") (pinfunction "1_1") (pintype "bidirectional"))
      (node (ref "R10") (pin "1") (pinfunction "1_1") (pintype "bidirectional"))
      (node (ref "U1") (pin "7") (pinfunction "WP_7") (pintype "bidirectional"))
    )
    (net (code "107") (name "VCC") (class "Default")
      (node (ref "BB.CAPE2") (pin "B9.3") (pinfunction "VDD.3V3(1)_B9.3") (pintype "bidirectional"))
      (node (ref "BB.CAPE2") (pin "B9.4") (pinfunction "VDD.3V3(2)_B9.4") (pintype "bidirectional"))
      (node (ref "BB.CAPE2") (pin "T9.3") (pinfunction "VDD.3V3(1)_T9.3") (pintype "bidirectional"))
      (node (ref "BB.CAPE2") (pin "T9.4") (pinfunction "VDD.3V3(2)_T9.4") (pintype "bidirectional"))
      (node (ref "C1") (pin "1") (pinfunction "1_1") (pintype "bidirectional"))
      (node (ref "C2") (pin "1") (pinfunction "1_1") (pintype "bidirectional"))
      (node (ref "R1") (pin "1") (pinfunction "1_1") (pintype "bidirectional"))
      (node (ref "R10") (pin "2") (pinfunction "2_2") (pintype "bidirectional"))
      (node (ref "R11") (pin "2") (pinfunction "2_2") (pintype "bidirectional"))
      (node (ref "R12") (pin "2") (pinfunction "2_2") (pintype "bidirectional"))
      (node (ref "R2") (pin "1") (pinfunction "1_1") (pintype "bidirectional"))
      (node (ref "R3") (pin "1") (pinfunction "1_1") (pintype "bidirectional"))
      (node (ref "R4") (pin "1") (pinfunction "1_1") (pintype "bidirectional"))
      (node (ref "R5") (pin "1") (pinfunction "1_1") (pintype "bidirectional"))
      (node (ref "R6") (pin "1") (pinfunction "1_1") (pintype "bidirectional"))
      (node (ref "R9") (pin "1") (pinfunction "1_1") (pintype "bidirectional"))
      (node (ref "SJ1") (pin "1") (pinfunction "1_1") (pintype "bidirectional"))
      (node (ref "SJ2") (pin "1") (pinfunction "1_1") (pintype "bidirectional"))
      (node (ref "U1") (pin "8") (pinfunction "VCC_8") (pintype "bidirectional"))
      (node (ref "U2") (pin "28") (pinfunction "VDD_28") (pintype "bidirectional"))
    )
    (net (code "108") (name "VIN") (class "Default")
      (node (ref "S1") (pin "2") (pinfunction "2_2") (pintype "passive"))
      (node (ref "S10") (pin "2") (pinfunction "2_2") (pintype "passive"))
      (node (ref "S11") (pin "2") (pinfunction "2_2") (pintype "passive"))
      (node (ref "S12") (pin "2") (pinfunction "2_2") (pintype "passive"))
      (node (ref "S13") (pin "2") (pinfunction "2_2") (pintype "passive"))
      (node (ref "S14") (pin "2") (pinfunction "2_2") (pintype "passive"))
      (node (ref "S15") (pin "2") (pinfunction "2_2") (pintype "passive"))
      (node (ref "S16") (pin "2") (pinfunction "2_2") (pintype "passive"))
      (node (ref "S2") (pin "2") (pinfunction "2_2") (pintype "passive"))
      (node (ref "S3") (pin "2") (pinfunction "2_2") (pintype "passive"))
      (node (ref "S4") (pin "2") (pinfunction "2_2") (pintype "passive"))
      (node (ref "S5") (pin "2") (pinfunction "2_2") (pintype "passive"))
      (node (ref "S6") (pin "2") (pinfunction "2_2") (pintype "passive"))
      (node (ref "S7") (pin "2") (pinfunction "2_2") (pintype "passive"))
      (node (ref "S8") (pin "2") (pinfunction "2_2") (pintype "passive"))
      (node (ref "S9") (pin "2") (pinfunction "2_2") (pintype "passive"))
      (node (ref "X1") (pin "1") (pinfunction "1_1") (pintype "bidirectional"))
    )
    (net (code "109") (name "VOUT") (class "Default")
      (node (ref "BB.CAPE2") (pin "B9.7") (pinfunction "SYS.5V(1)_B9.7") (pintype "bidirectional"))
      (node (ref "BB.CAPE2") (pin "B9.8") (pinfunction "SYS.5V(2)_B9.8") (pintype "bidirectional"))
      (node (ref "BB.CAPE2") (pin "T9.7") (pinfunction "SYS.5V(1)_T9.7") (pintype "bidirectional"))
      (node (ref "BB.CAPE2") (pin "T9.8") (pinfunction "SYS.5V(2)_T9.8") (pintype "bidirectional"))
      (node (ref "X2") (pin "2") (pinfunction "2_2") (pintype "passive"))
    )
    (net (code "110") (name "unconnected-(FUD1-PadP$1)") (class "Default")
      (node (ref "FUD1") (pin "P$1") (pinfunction "P$1_P$1") (pintype "no_connect"))
    )
    (net (code "111") (name "unconnected-(FUD2-PadP$1)") (class "Default")
      (node (ref "FUD2") (pin "P$1") (pinfunction "P$1_P$1") (pintype "no_connect"))
    )
    (net (code "112") (name "unconnected-(FUD3-PadP$1)") (class "Default")
      (node (ref "FUD3") (pin "P$1") (pinfunction "P$1_P$1") (pintype "no_connect"))
    )
    (net (code "113") (name "unconnected-(FUD4-PadP$1)") (class "Default")
      (node (ref "FUD4") (pin "P$1") (pinfunction "P$1_P$1") (pintype "no_connect"))
    )
    (net (code "114") (name "unconnected-(FUD5-PadP$1)") (class "Default")
      (node (ref "FUD5") (pin "P$1") (pinfunction "P$1_P$1") (pintype "no_connect"))
    )
    (net (code "115") (name "unconnected-(FUD6-PadP$1)") (class "Default")
      (node (ref "FUD6") (pin "P$1") (pinfunction "P$1_P$1") (pintype "no_connect"))
    )
    (net (code "116") (name "unconnected-(IN1-Pad2)") (class "Default")
      (node (ref "IN1") (pin "2") (pinfunction "2_2") (pintype "passive"))
    )
    (net (code "117") (name "unconnected-(IN2-Pad2)") (class "Default")
      (node (ref "IN2") (pin "2") (pinfunction "2_2") (pintype "passive"))
    )
    (net (code "118") (name "unconnected-(IN3-Pad2)") (class "Default")
      (node (ref "IN3") (pin "2") (pinfunction "2_2") (pintype "passive"))
    )
    (net (code "119") (name "unconnected-(IN4-Pad2)") (class "Default")
      (node (ref "IN4") (pin "2") (pinfunction "2_2") (pintype "passive"))
    )
    (net (code "120") (name "unconnected-(IN5-Pad2)") (class "Default")
      (node (ref "IN5") (pin "2") (pinfunction "2_2") (pintype "passive"))
    )
    (net (code "121") (name "unconnected-(IN6-Pad2)") (class "Default")
      (node (ref "IN6") (pin "2") (pinfunction "2_2") (pintype "passive"))
    )
  )
)
